# Sheet2.net
KiCad netlist of a schematic drawn in Altium Designer
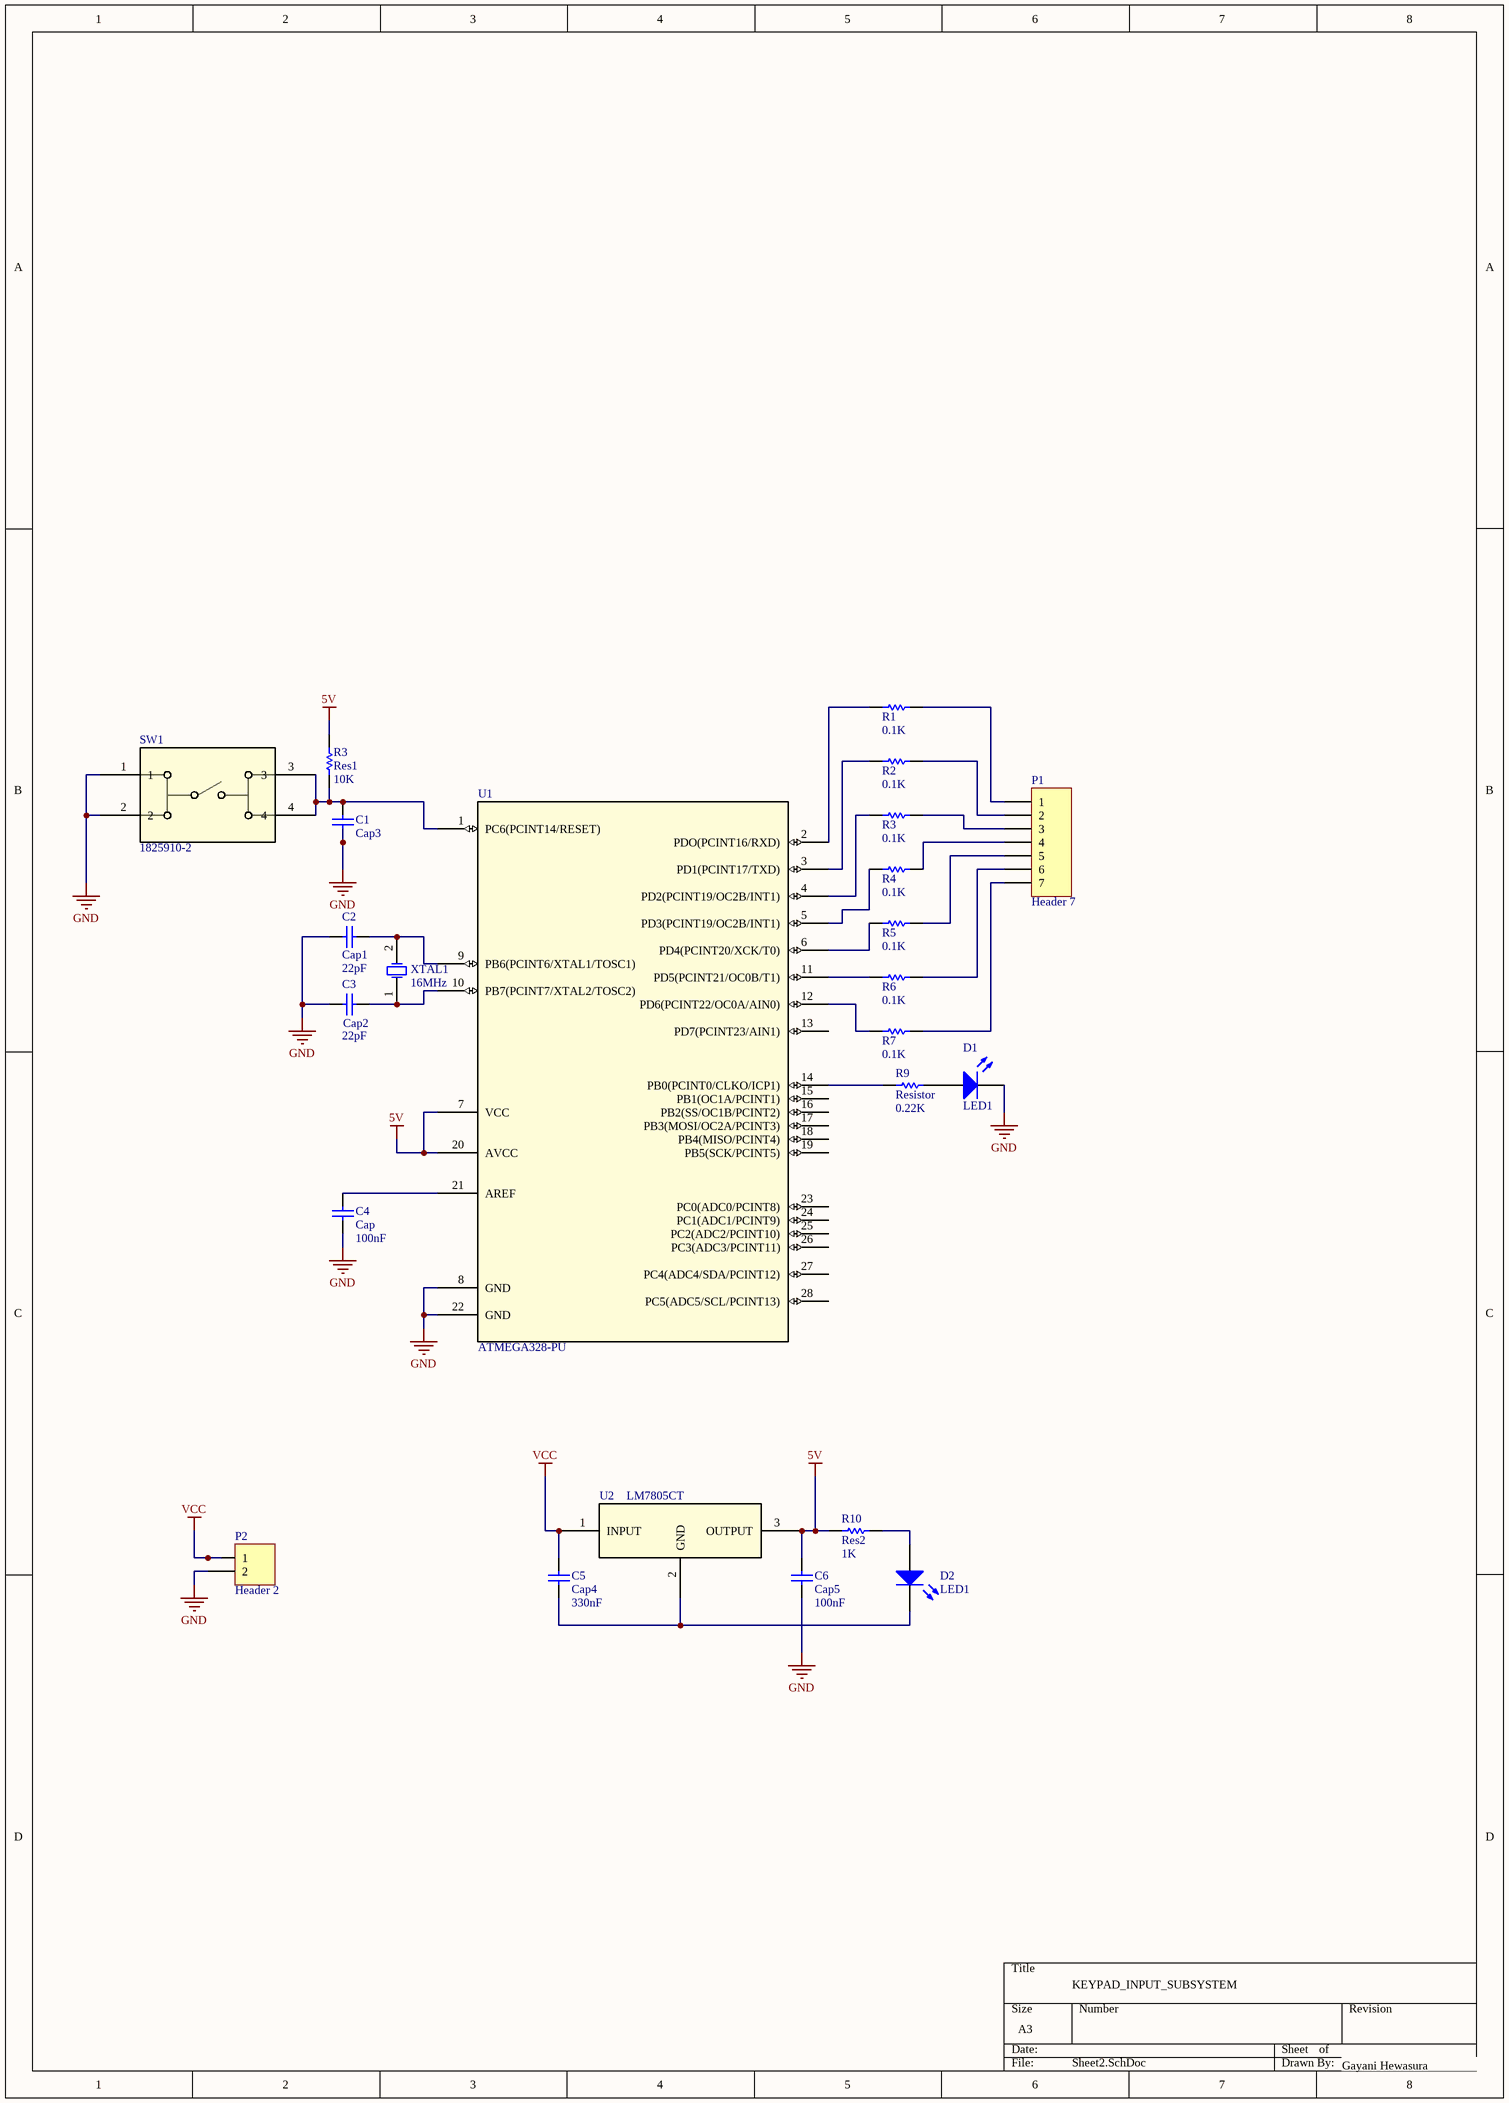
[diagram p0: Sheet2.SchDoc]

(export (version "E")
  (design (tool "Eeschema 10.0.6"))
  (components
    (comp (ref "C1")
      (value "Cap3")
      (footprint "RAD-0.3")
      (description "Capacitor")
      (fields (field (name "PUBLISHER") "Altium Limited"))
      (libsource (lib "Miscellaneous Devices") (part "Cap"))
    )
    (comp (ref "C2")
      (value "Cap1")
      (footprint "RAD-0.3")
      (description "Capacitor")
      (fields (field (name "ALTIUM_VALUE") "22pF") (field (name "PUBLISHER") "Altium Limited"))
      (libsource (lib "Miscellaneous Devices") (part "Cap"))
    )
    (comp (ref "C3")
      (value "Cap2")
      (footprint "RAD-0.3")
      (description "Capacitor")
      (fields (field (name "ALTIUM_VALUE") "22pF") (field (name "PUBLISHER") "Altium Limited"))
      (libsource (lib "Miscellaneous Devices") (part "Cap"))
    )
    (comp (ref "C4")
      (value "Cap")
      (footprint "RAD-0.3")
      (description "Capacitor")
      (fields (field (name "ALTIUM_VALUE") "100nF") (field (name "PUBLISHER") "Altium Limited"))
      (libsource (lib "Miscellaneous Devices") (part "Cap"))
    )
    (comp (ref "C5")
      (value "Cap4")
      (footprint "RAD-0.3")
      (description "Capacitor")
      (fields (field (name "ALTIUM_VALUE") "330nF") (field (name "PUBLISHER") "Altium Limited"))
      (libsource (lib "Miscellaneous Devices") (part "Cap"))
    )
    (comp (ref "C6")
      (value "Cap5")
      (footprint "RAD-0.3")
      (description "Capacitor")
      (fields (field (name "ALTIUM_VALUE") "100nF") (field (name "PUBLISHER") "Altium Limited"))
      (libsource (lib "Miscellaneous Devices") (part "Cap"))
    )
    (comp (ref "D1")
      (value "LED1")
      (footprint "LED-1")
      (description "Typical RED GaAs LED")
      (fields (field (name "PUBLISHER") "Altium Limited"))
      (libsource (lib "Miscellaneous Devices") (part "LED1"))
    )
    (comp (ref "D2")
      (value "LED1")
      (footprint "LED-1")
      (description "Typical RED GaAs LED")
      (fields (field (name "PUBLISHER") "Altium Limited"))
      (libsource (lib "Miscellaneous Devices") (part "LED1"))
    )
    (comp (ref "P1")
      (value "Header 7")
      (footprint "HDR1X7")
      (description "Header, 7-Pin")
      (fields (field (name "PUBLISHER") "Altium Limited"))
      (libsource (lib "Miscellaneous Connectors") (part "Header 7"))
    )
    (comp (ref "P2")
      (value "Header 2")
      (footprint "HDR1X2")
      (description "Header, 2-Pin")
      (fields (field (name "PUBLISHER") "Altium Limited"))
      (libsource (lib "Miscellaneous Connectors") (part "Header 2"))
    )
    (comp (ref "R1")
      (value "R1")
      (footprint "AXIAL-0.3")
      (description "Resistor")
      (fields (field (name "ALTIUM_VALUE") "0.1K") (field (name "PUBLISHER") "Altium Limited"))
      (libsource (lib "Miscellaneous Devices") (part "Res1"))
    )
    (comp (ref "R2")
      (value "R2")
      (footprint "AXIAL-0.3")
      (description "Resistor")
      (fields (field (name "ALTIUM_VALUE") "0.1K") (field (name "PUBLISHER") "Altium Limited"))
      (libsource (lib "Miscellaneous Devices") (part "Res1"))
    )
    (comp (ref "R3")
      (value "Res1")
      (footprint "AXIAL-0.3")
      (description "Resistor")
      (fields (field (name "ALTIUM_VALUE") "10K") (field (name "PUBLISHER") "Altium Limited"))
      (libsource (lib "Miscellaneous Devices") (part "Res1"))
    )
    (comp (ref "R4")
      (value "R3")
      (footprint "AXIAL-0.3")
      (description "Resistor")
      (fields (field (name "ALTIUM_VALUE") "0.1K") (field (name "PUBLISHER") "Altium Limited"))
      (libsource (lib "Miscellaneous Devices") (part "Res1"))
    )
    (comp (ref "R5")
      (value "R4")
      (footprint "AXIAL-0.3")
      (description "Resistor")
      (fields (field (name "ALTIUM_VALUE") "0.1K") (field (name "PUBLISHER") "Altium Limited"))
      (libsource (lib "Miscellaneous Devices") (part "Res1"))
    )
    (comp (ref "R6")
      (value "R5")
      (footprint "AXIAL-0.3")
      (description "Resistor")
      (fields (field (name "ALTIUM_VALUE") "0.1K") (field (name "PUBLISHER") "Altium Limited"))
      (libsource (lib "Miscellaneous Devices") (part "Res1"))
    )
    (comp (ref "R7")
      (value "R6")
      (footprint "AXIAL-0.3")
      (description "Resistor")
      (fields (field (name "ALTIUM_VALUE") "0.1K") (field (name "PUBLISHER") "Altium Limited"))
      (libsource (lib "Miscellaneous Devices") (part "Res1"))
    )
    (comp (ref "R8")
      (value "R7")
      (footprint "AXIAL-0.3")
      (description "Resistor")
      (fields (field (name "ALTIUM_VALUE") "0.1K") (field (name "PUBLISHER") "Altium Limited"))
      (libsource (lib "Miscellaneous Devices") (part "Res1"))
    )
    (comp (ref "R9")
      (value "Resistor")
      (footprint "AXIAL-0.3")
      (fields (field (name "ALTIUM_VALUE") "0.22K") (field (name "PUBLISHER") "Altium Limited"))
      (libsource (lib "Miscellaneous Devices") (part "Res1"))
    )
    (comp (ref "R10")
      (value "Res2")
      (footprint "AXIAL-0.3")
      (description "Resistor")
      (fields (field (name "ALTIUM_VALUE") "1K") (field (name "PUBLISHER") "Altium Limited"))
      (libsource (lib "Miscellaneous Devices") (part "Res1"))
    )
    (comp (ref "SW1")
      (value "1825910-2")
      (footprint "SW4_1825910-A_TEC")
      (description "FSM2JH=6MM TACT SWITCH, HIGH TEMP")
      (fields (field (name "COPYRIGHT") "Copyright (C) 2016 Accelerated Designs. All rights reserved"))
      (libsource (lib "tactile") (part "1825910-2"))
    )
    (comp (ref "U1")
      (value "ATMEGA328-PU")
      (footprint "28P3_SPDIP28_SP_MCH")
      (description "No Description Available")
      (fields (field (name "COPYRIGHT") "Copyright (C) 2018 Accelerated Designs. All rights reserved"))
      (libsource (lib "ATmega328P") (part "ATMEGA328-PU"))
    )
    (comp (ref "U2")
      (value "LM7805CT")
      (footprint "TO-220_FAS")
      (description "No Description Available")
      (fields (field (name "COPYRIGHT") "Copyright (C) 2018 Accelerated Designs. All rights reserved"))
      (libsource (lib "LM7805") (part "LM7805CT"))
    )
    (comp (ref "Y1")
      (value "XTAL1")
      (footprint "R38")
      (description "Crystal Oscillator")
      (fields (field (name "ALTIUM_VALUE") "16MHz") (field (name "PUBLISHER") "Altium Limited"))
      (libsource (lib "Miscellaneous Devices") (part "XTAL"))
    )
  )
  (nets
    (net (code "1") (name "5V") (class "Default")
      (node (ref "C6") (pin "2") (pinfunction "2_2") (pintype "passive"))
      (node (ref "R10") (pin "1") (pinfunction "1_1") (pintype "passive"))
      (node (ref "R3") (pin "2") (pinfunction "2_2") (pintype "passive"))
      (node (ref "U1") (pin "20") (pinfunction "AVCC_20") (pintype "power_in"))
      (node (ref "U1") (pin "7") (pinfunction "VCC_7") (pintype "power_in"))
      (node (ref "U2") (pin "3") (pinfunction "OUTPUT_3") (pintype "power_in"))
    )
    (net (code "2") (name "GND") (class "Default")
      (node (ref "C1") (pin "1") (pinfunction "1_1") (pintype "passive"))
      (node (ref "C2") (pin "1") (pinfunction "1_1") (pintype "passive"))
      (node (ref "C3") (pin "1") (pinfunction "1_1") (pintype "passive"))
      (node (ref "C4") (pin "1") (pinfunction "1_1") (pintype "passive"))
      (node (ref "C6") (pin "1") (pinfunction "1_1") (pintype "passive"))
      (node (ref "D1") (pin "2") (pinfunction "K_2") (pintype "passive"))
      (node (ref "P2") (pin "2") (pinfunction "2_2") (pintype "passive"))
      (node (ref "SW1") (pin "1") (pinfunction "1_1") (pintype "passive"))
      (node (ref "SW1") (pin "2") (pinfunction "2_2") (pintype "passive"))
      (node (ref "U1") (pin "22") (pinfunction "GND_22") (pintype "passive"))
      (node (ref "U1") (pin "8") (pinfunction "GND_8") (pintype "passive"))
    )
    (net (code "3") (name "Net-(D1-A)") (class "Default")
      (node (ref "D1") (pin "1") (pinfunction "A_1") (pintype "passive"))
      (node (ref "R9") (pin "2") (pinfunction "2_2") (pintype "passive"))
    )
    (net (code "4") (name "Net-(D2-A)") (class "Default")
      (node (ref "D2") (pin "1") (pinfunction "A_1") (pintype "passive"))
      (node (ref "R10") (pin "2") (pinfunction "2_2") (pintype "passive"))
    )
    (net (code "5") (name "Net-(D2-K)") (class "Default")
      (node (ref "C5") (pin "1") (pinfunction "1_1") (pintype "passive"))
      (node (ref "D2") (pin "2") (pinfunction "K_2") (pintype "passive"))
      (node (ref "U2") (pin "2") (pinfunction "GND_2") (pintype "power_in"))
    )
    (net (code "6") (name "Net-(P1-Pad1)") (class "Default")
      (node (ref "P1") (pin "1") (pinfunction "1_1") (pintype "passive"))
      (node (ref "R1") (pin "2") (pinfunction "2_2") (pintype "passive"))
    )
    (net (code "7") (name "Net-(P1-Pad2)") (class "Default")
      (node (ref "P1") (pin "2") (pinfunction "2_2") (pintype "passive"))
      (node (ref "R2") (pin "2") (pinfunction "2_2") (pintype "passive"))
    )
    (net (code "8") (name "Net-(P1-Pad3)") (class "Default")
      (node (ref "P1") (pin "3") (pinfunction "3_3") (pintype "passive"))
      (node (ref "R4") (pin "2") (pinfunction "2_2") (pintype "passive"))
    )
    (net (code "9") (name "Net-(P1-Pad4)") (class "Default")
      (node (ref "P1") (pin "4") (pinfunction "4_4") (pintype "passive"))
      (node (ref "R5") (pin "2") (pinfunction "2_2") (pintype "passive"))
    )
    (net (code "10") (name "Net-(P1-Pad5)") (class "Default")
      (node (ref "P1") (pin "5") (pinfunction "5_5") (pintype "passive"))
      (node (ref "R6") (pin "2") (pinfunction "2_2") (pintype "passive"))
    )
    (net (code "11") (name "Net-(P1-Pad6)") (class "Default")
      (node (ref "P1") (pin "6") (pinfunction "6_6") (pintype "passive"))
      (node (ref "R7") (pin "2") (pinfunction "2_2") (pintype "passive"))
    )
    (net (code "12") (name "Net-(P1-Pad7)") (class "Default")
      (node (ref "P1") (pin "7") (pinfunction "7_7") (pintype "passive"))
      (node (ref "R8") (pin "2") (pinfunction "2_2") (pintype "passive"))
    )
    (net (code "13") (name "Net-(U1-AREF)") (class "Default")
      (node (ref "C4") (pin "2") (pinfunction "2_2") (pintype "passive"))
      (node (ref "U1") (pin "21") (pinfunction "AREF_21") (pintype "passive"))
    )
    (net (code "14") (name "Net-(U1-PB0(PCINT0{slash}CLKO{slash}ICP1))") (class "Default")
      (node (ref "R9") (pin "1") (pinfunction "1_1") (pintype "passive"))
      (node (ref "U1") (pin "14") (pinfunction "PB0(PCINT0/CLKO/ICP1)_14") (pintype "bidirectional"))
    )
    (net (code "15") (name "Net-(U1-PB6(PCINT6{slash}XTAL1{slash}TOSC1))") (class "Default")
      (node (ref "C2") (pin "2") (pinfunction "2_2") (pintype "passive"))
      (node (ref "U1") (pin "9") (pinfunction "PB6(PCINT6/XTAL1/TOSC1)_9") (pintype "bidirectional"))
      (node (ref "Y1") (pin "2") (pinfunction "OSC2_2") (pintype "passive"))
    )
    (net (code "16") (name "Net-(U1-PB7(PCINT7{slash}XTAL2{slash}TOSC2))") (class "Default")
      (node (ref "C3") (pin "2") (pinfunction "2_2") (pintype "passive"))
      (node (ref "U1") (pin "10") (pinfunction "PB7(PCINT7/XTAL2/TOSC2)_10") (pintype "bidirectional"))
      (node (ref "Y1") (pin "1") (pinfunction "OSC1_1") (pintype "passive"))
    )
    (net (code "17") (name "Net-(U1-PC6(PCINT14{slash}RESET))") (class "Default")
      (node (ref "C1") (pin "2") (pinfunction "2_2") (pintype "passive"))
      (node (ref "R3") (pin "1") (pinfunction "1_1") (pintype "passive"))
      (node (ref "SW1") (pin "3") (pinfunction "3_3") (pintype "passive"))
      (node (ref "SW1") (pin "4") (pinfunction "4_4") (pintype "passive"))
      (node (ref "U1") (pin "1") (pinfunction "PC6(PCINT14/RESET)_1") (pintype "bidirectional"))
    )
    (net (code "18") (name "Net-(U1-PD1(PCINT17{slash}TXD))") (class "Default")
      (node (ref "R2") (pin "1") (pinfunction "1_1") (pintype "passive"))
      (node (ref "U1") (pin "3") (pinfunction "PD1(PCINT17/TXD)_3") (pintype "bidirectional"))
    )
    (net (code "19") (name "Net-(U1-PD2(PCINT19{slash}OC2B{slash}INT1))") (class "Default")
      (node (ref "R4") (pin "1") (pinfunction "1_1") (pintype "passive"))
      (node (ref "U1") (pin "4") (pinfunction "PD2(PCINT19/OC2B/INT1)_4") (pintype "bidirectional"))
    )
    (net (code "20") (name "Net-(U1-PD3(PCINT19{slash}OC2B{slash}INT1))") (class "Default")
      (node (ref "R5") (pin "1") (pinfunction "1_1") (pintype "passive"))
      (node (ref "U1") (pin "5") (pinfunction "PD3(PCINT19/OC2B/INT1)_5") (pintype "bidirectional"))
    )
    (net (code "21") (name "Net-(U1-PD4(PCINT20{slash}XCK{slash}T0))") (class "Default")
      (node (ref "R6") (pin "1") (pinfunction "1_1") (pintype "passive"))
      (node (ref "U1") (pin "6") (pinfunction "PD4(PCINT20/XCK/T0)_6") (pintype "bidirectional"))
    )
    (net (code "22") (name "Net-(U1-PD5(PCINT21{slash}OC0B{slash}T1))") (class "Default")
      (node (ref "R7") (pin "1") (pinfunction "1_1") (pintype "passive"))
      (node (ref "U1") (pin "11") (pinfunction "PD5(PCINT21/OC0B/T1)_11") (pintype "bidirectional"))
    )
    (net (code "23") (name "Net-(U1-PD6(PCINT22{slash}OC0A{slash}AIN0))") (class "Default")
      (node (ref "R8") (pin "1") (pinfunction "1_1") (pintype "passive"))
      (node (ref "U1") (pin "12") (pinfunction "PD6(PCINT22/OC0A/AIN0)_12") (pintype "bidirectional"))
    )
    (net (code "24") (name "Net-(U1-PDO(PCINT16{slash}RXD))") (class "Default")
      (node (ref "R1") (pin "1") (pinfunction "1_1") (pintype "passive"))
      (node (ref "U1") (pin "2") (pinfunction "PDO(PCINT16/RXD)_2") (pintype "bidirectional"))
    )
    (net (code "25") (name "VCC") (class "Default")
      (node (ref "C5") (pin "2") (pinfunction "2_2") (pintype "passive"))
      (node (ref "P2") (pin "1") (pinfunction "1_1") (pintype "passive"))
      (node (ref "U2") (pin "1") (pinfunction "INPUT_1") (pintype "power_in"))
    )
    (net (code "26") (name "unconnected-(U1-PB1(OC1A{slash}PCINT1)-Pad15)") (class "Default")
      (node (ref "U1") (pin "15") (pinfunction "PB1(OC1A/PCINT1)_15") (pintype "bidirectional"))
    )
    (net (code "27") (name "unconnected-(U1-PB2(SS{slash}OC1B{slash}PCINT2)-Pad16)") (class "Default")
      (node (ref "U1") (pin "16") (pinfunction "PB2(SS/OC1B/PCINT2)_16") (pintype "bidirectional"))
    )
    (net (code "28") (name "unconnected-(U1-PB3(MOSI{slash}OC2A{slash}PCINT3)-Pad17)") (class "Default")
      (node (ref "U1") (pin "17") (pinfunction "PB3(MOSI/OC2A/PCINT3)_17") (pintype "bidirectional"))
    )
    (net (code "29") (name "unconnected-(U1-PB4(MISO{slash}PCINT4)-Pad18)") (class "Default")
      (node (ref "U1") (pin "18") (pinfunction "PB4(MISO/PCINT4)_18") (pintype "bidirectional"))
    )
    (net (code "30") (name "unconnected-(U1-PB5(SCK{slash}PCINT5)-Pad19)") (class "Default")
      (node (ref "U1") (pin "19") (pinfunction "PB5(SCK/PCINT5)_19") (pintype "bidirectional"))
    )
    (net (code "31") (name "unconnected-(U1-PC0(ADC0{slash}PCINT8)-Pad23)") (class "Default")
      (node (ref "U1") (pin "23") (pinfunction "PC0(ADC0/PCINT8)_23") (pintype "bidirectional"))
    )
    (net (code "32") (name "unconnected-(U1-PC1(ADC1{slash}PCINT9)-Pad24)") (class "Default")
      (node (ref "U1") (pin "24") (pinfunction "PC1(ADC1/PCINT9)_24") (pintype "bidirectional"))
    )
    (net (code "33") (name "unconnected-(U1-PC2(ADC2{slash}PCINT10)-Pad25)") (class "Default")
      (node (ref "U1") (pin "25") (pinfunction "PC2(ADC2/PCINT10)_25") (pintype "bidirectional"))
    )
    (net (code "34") (name "unconnected-(U1-PC3(ADC3{slash}PCINT11)-Pad26)") (class "Default")
      (node (ref "U1") (pin "26") (pinfunction "PC3(ADC3/PCINT11)_26") (pintype "bidirectional"))
    )
    (net (code "35") (name "unconnected-(U1-PC4(ADC4{slash}SDA{slash}PCINT12)-Pad27)") (class "Default")
      (node (ref "U1") (pin "27") (pinfunction "PC4(ADC4/SDA/PCINT12)_27") (pintype "bidirectional"))
    )
    (net (code "36") (name "unconnected-(U1-PC5(ADC5{slash}SCL{slash}PCINT13)-Pad28)") (class "Default")
      (node (ref "U1") (pin "28") (pinfunction "PC5(ADC5/SCL/PCINT13)_28") (pintype "bidirectional"))
    )
    (net (code "37") (name "unconnected-(U1-PD7(PCINT23{slash}AIN1)-Pad13)") (class "Default")
      (node (ref "U1") (pin "13") (pinfunction "PD7(PCINT23/AIN1)_13") (pintype "bidirectional"))
    )
  )
)
